# SHDN-CURRENT-S05-V00-CurrentInterface.net
KiCad netlist of a schematic drawn in Altium Designer
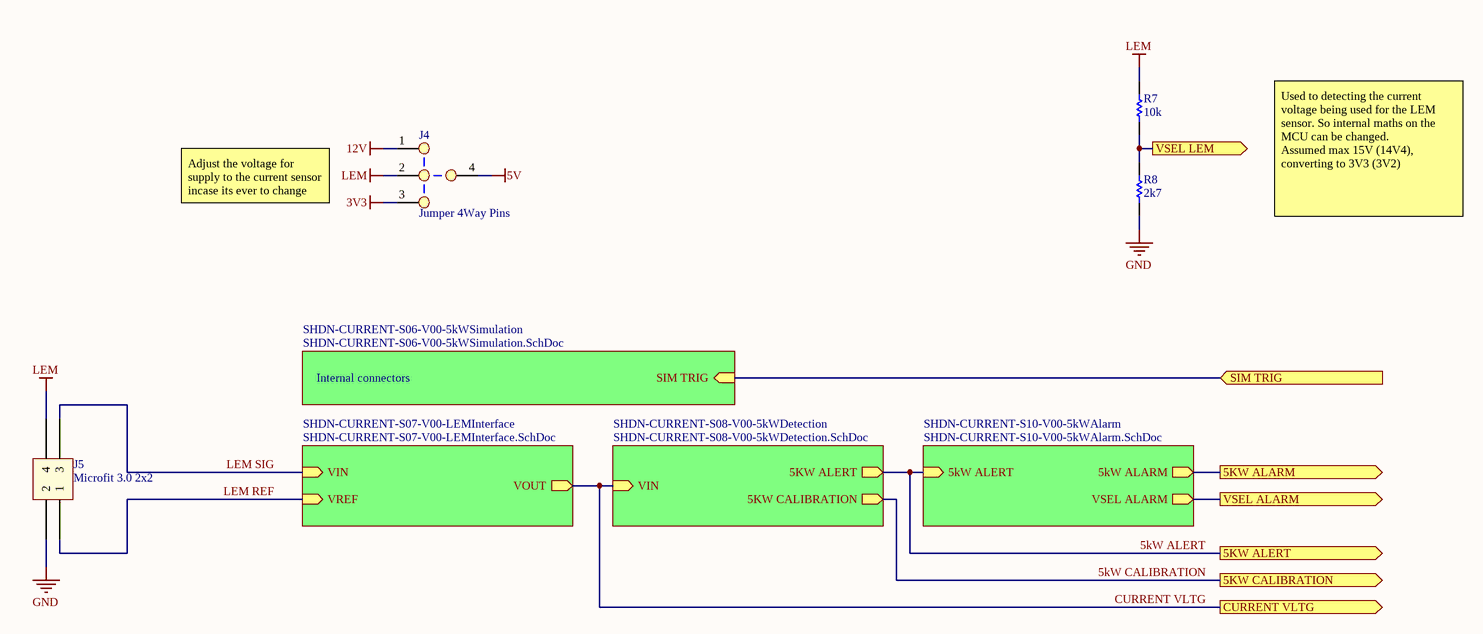
[diagram p0: SHDN-CURRENT-S05-V00-CurrentInterface.SchDoc]

(export (version "E")
  (design (tool "Eeschema 10.0.6"))
  (components
    (comp (ref "J4")
      (value "Jumper 4Way Pins")
      (footprint "Jumper_4Way_Pin")
      (libsource (lib "QUTMS_JumperLibrary") (part "Jumper 4Way Pins"))
    )
    (comp (ref "J5")
      (value "Microfit 3.0 2x2")
      (footprint "Microfit_2X2_R_TH")
      (libsource (lib "QUTMS_MicrofitLibrary") (part "Microfit_2x2"))
    )
    (comp (ref "R7")
      (value "10k")
      (footprint "Res_ThinFilm_0603")
      (description "Resistor, SMD, 10k, 0.1W, 5%, 0603")
      (libsource (lib "StandardResistors") (part "10k 5% 0603"))
    )
    (comp (ref "R8")
      (value "2k7")
      (footprint "Res_ThinFilm_0603")
      (description "Resistor, SMD, 2k7, 0.1W, 5%, 0603")
      (libsource (lib "StandardResistors") (part "2k7 5% 0603"))
    )
  )
  (nets
    (net (code "5") (name "/LEM REF") (class "Default")
      (node (ref "J5") (pin "1") (pinfunction "1_1") (pintype "passive"))
    )
    (net (code "6") (name "/LEM SIG") (class "Default")
      (node (ref "J5") (pin "3") (pinfunction "3_3") (pintype "passive"))
    )
    (net (code "9") (name "/VSEL LEM") (class "Default")
      (node (ref "R7") (pin "1") (pinfunction "1_1") (pintype "passive"))
      (node (ref "R8") (pin "2") (pinfunction "2_2") (pintype "passive"))
    )
    (net (code "10") (name "3V3") (class "Default")
      (node (ref "J4") (pin "3") (pinfunction "3_3") (pintype "passive"))
    )
    (net (code "11") (name "5V") (class "Default")
      (node (ref "J4") (pin "4") (pinfunction "4_4") (pintype "passive"))
    )
    (net (code "12") (name "12V") (class "Default")
      (node (ref "J4") (pin "1") (pinfunction "1_1") (pintype "passive"))
    )
    (net (code "13") (name "GND") (class "Default")
      (node (ref "J5") (pin "2") (pinfunction "2_2") (pintype "passive"))
      (node (ref "R8") (pin "1") (pinfunction "1_1") (pintype "passive"))
    )
    (net (code "14") (name "LEM") (class "Default")
      (node (ref "J4") (pin "2") (pinfunction "2_2") (pintype "passive"))
      (node (ref "J5") (pin "4") (pinfunction "4_4") (pintype "passive"))
      (node (ref "R7") (pin "2") (pinfunction "2_2") (pintype "passive"))
    )
  )
)
